# communicator_v2p5.net
KiCad netlist of a schematic drawn in EAGLE
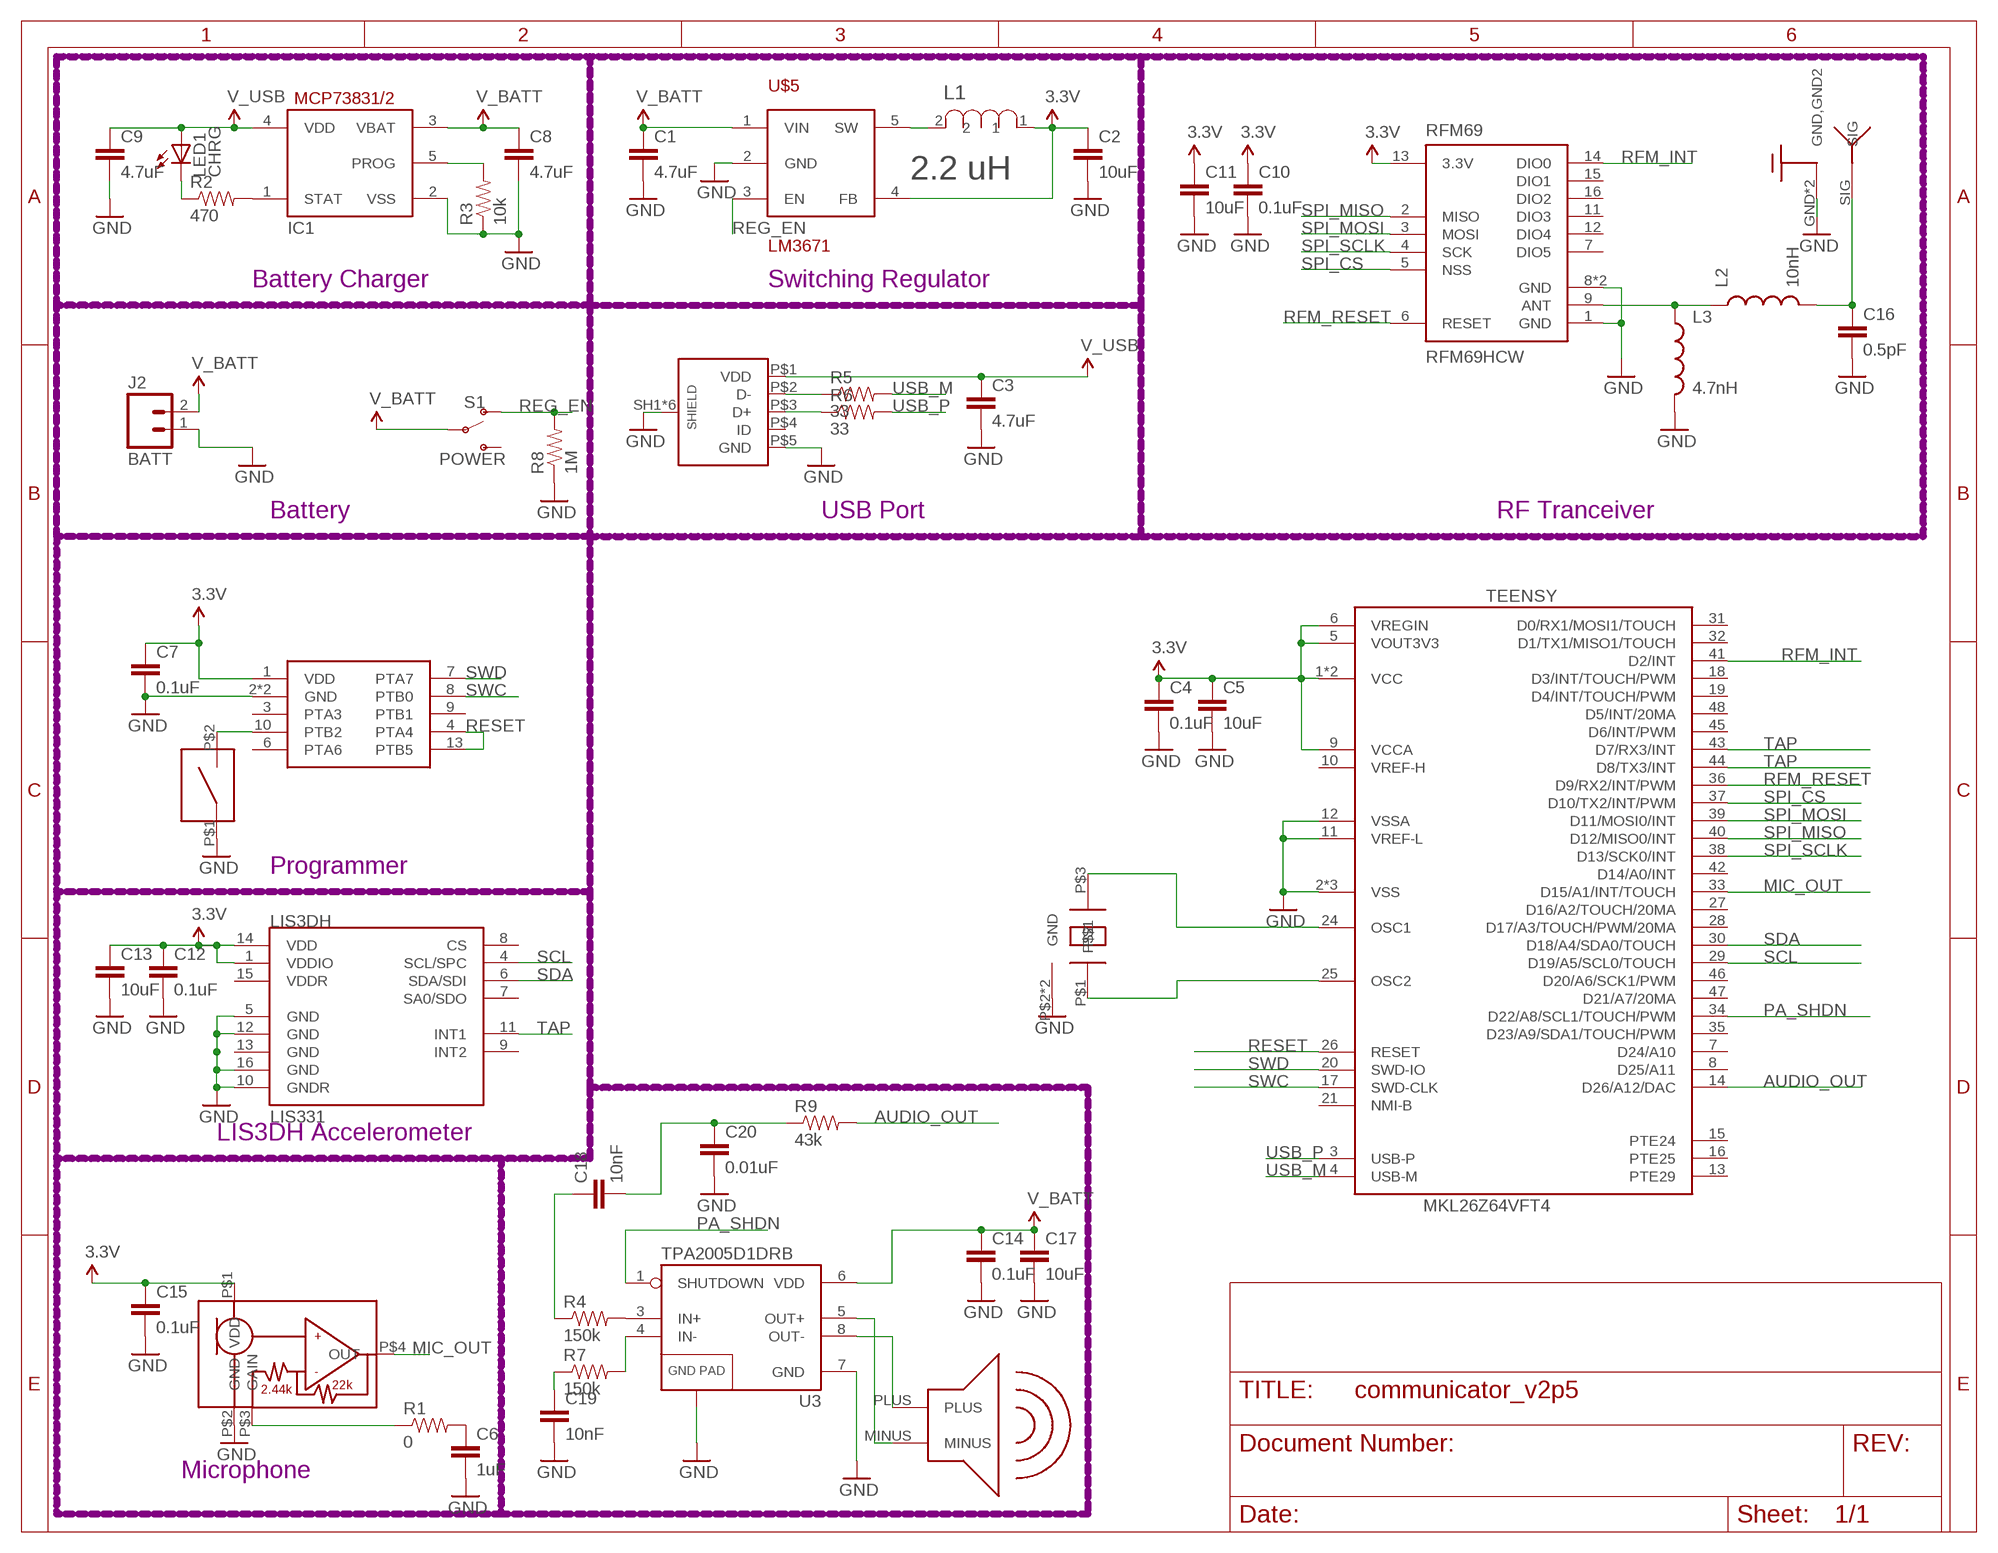
[diagram p0: schematic, sheet 1]

(export (version "E")
  (design (tool "Eeschema 10.0.6"))
  (components
    (comp (ref "3X3MM1")
      (value "CURRENT_BOOTLOADER3X3MM")
      (footprint "eagle-import:QFN50P300X300X100-17N")
      (libsource (lib "eagle-import") (part "CURRENT_BOOTLOADER3X3MM"))
    )
    (comp (ref "C1")
      (value "4.7uF")
      (footprint "eagle-import:0603-CAP")
      (libsource (lib "eagle-import") (part "0.1UF-25V(+80/-20%)(0603)"))
    )
    (comp (ref "C2")
      (value "10uF")
      (footprint "eagle-import:0603-CAP")
      (libsource (lib "eagle-import") (part "2.2UF-10V-20%(0603)"))
    )
    (comp (ref "C3")
      (value "4.7uF")
      (footprint "eagle-import:0603-CAP")
      (libsource (lib "eagle-import") (part "2.2UF-10V-20%(0603)"))
    )
    (comp (ref "C4")
      (value "0.1uF")
      (footprint "eagle-import:0603-CAP")
      (libsource (lib "eagle-import") (part "0.1UF-25V(+80/-20%)(0603)"))
    )
    (comp (ref "C5")
      (value "10uF")
      (footprint "eagle-import:0603-CAP")
      (libsource (lib "eagle-import") (part "10UF-6.3V-20%(0603)"))
    )
    (comp (ref "C6")
      (value "1uF")
      (footprint "eagle-import:0603-CAP")
      (libsource (lib "eagle-import") (part "0.1UF-25V(+80/-20%)(0603)"))
    )
    (comp (ref "C7")
      (value "0.1uF")
      (footprint "eagle-import:0603-CAP")
      (libsource (lib "eagle-import") (part "0.1UF-25V(+80/-20%)(0603)"))
    )
    (comp (ref "C8")
      (value "4.7uF")
      (footprint "eagle-import:0603-CAP")
      (libsource (lib "eagle-import") (part "4.7UF-6.3V-10%(0603)0603"))
    )
    (comp (ref "C9")
      (value "4.7uF")
      (footprint "eagle-import:0603-CAP")
      (libsource (lib "eagle-import") (part "4.7UF-6.3V-10%(0603)0603"))
    )
    (comp (ref "C10")
      (value "0.1uF")
      (footprint "eagle-import:0603-CAP")
      (libsource (lib "eagle-import") (part "0.1UF-25V(+80/-20%)(0603)"))
    )
    (comp (ref "C11")
      (value "10uF")
      (footprint "eagle-import:0603-CAP")
      (libsource (lib "eagle-import") (part "10UF-6.3V-20%(0603)"))
    )
    (comp (ref "C12")
      (value "0.1uF")
      (footprint "eagle-import:0603-CAP")
      (libsource (lib "eagle-import") (part "0.1UF-25V(+80/-20%)(0603)"))
    )
    (comp (ref "C13")
      (value "10uF")
      (footprint "eagle-import:0603-CAP")
      (libsource (lib "eagle-import") (part "10UF-6.3V-20%(0603)"))
    )
    (comp (ref "C14")
      (value "0.1uF")
      (footprint "eagle-import:0603-CAP")
      (libsource (lib "eagle-import") (part "0.1UF-25V(+80/-20%)(0603)"))
    )
    (comp (ref "C15")
      (value "0.1uF")
      (footprint "eagle-import:0603-CAP")
      (libsource (lib "eagle-import") (part "0.1UF-25V(+80/-20%)(0603)"))
    )
    (comp (ref "C16")
      (value "0.5pF")
      (footprint "eagle-import:0603-CAP")
      (libsource (lib "eagle-import") (part "0.75PF-50V(-/+.25PF)(0603)"))
    )
    (comp (ref "C17")
      (value "10uF")
      (footprint "eagle-import:0603-CAP")
      (libsource (lib "eagle-import") (part "10UF-6.3V-20%(0603)"))
    )
    (comp (ref "C18")
      (value "10nF")
      (footprint "eagle-import:0603-CAP")
      (libsource (lib "eagle-import") (part "0.1UF-25V(+80/-20%)(0603)"))
    )
    (comp (ref "C19")
      (value "10nF")
      (footprint "eagle-import:0603-CAP")
      (libsource (lib "eagle-import") (part "0.1UF-25V(+80/-20%)(0603)"))
    )
    (comp (ref "C20")
      (value "0.01uF")
      (footprint "eagle-import:0603-CAP")
      (libsource (lib "eagle-import") (part "0.1UF-25V(+80/-20%)(0603)"))
    )
    (comp (ref "IC1")
      (value "MCP73831/OT")
      (footprint "eagle-import:SOT23-5L")
      (libsource (lib "eagle-import") (part "MCP73831/OT"))
    )
    (comp (ref "J2")
      (value "BATT")
      (footprint "eagle-import:1X02")
      (libsource (lib "eagle-import") (part "M02PTH"))
    )
    (comp (ref "L1")
      (value "2.2 uH")
      (footprint "eagle-import:INDC3225X22N")
      (fields (field (name "MPN") "PM1210-2R2J-RC") (field (name "TOLERANCE") "±5 %"))
      (libsource (lib "eagle-import") (part "PM1210-2R2J-RC"))
    )
    (comp (ref "L2")
      (value "10nH")
      (footprint "eagle-import:0603")
      (libsource (lib "eagle-import") (part "INDUCTOR0603"))
    )
    (comp (ref "L3")
      (value "4.7nH")
      (footprint "eagle-import:0603")
      (libsource (lib "eagle-import") (part "INDUCTOR0603"))
    )
    (comp (ref "LED1")
      (value "CHRG")
      (footprint "eagle-import:CHIPLED_0805")
      (libsource (lib "eagle-import") (part "LEDCHIPLED_0805"))
    )
    (comp (ref "LIS3DH")
      (value "LIS331")
      (footprint "eagle-import:LGA16-3MM")
      (libsource (lib "eagle-import") (part "LIS331"))
    )
    (comp (ref "R1")
      (value "0")
      (footprint "eagle-import:0603-RES")
      (libsource (lib "eagle-import") (part "33OHM1/10W1%(0603)"))
    )
    (comp (ref "R2")
      (value "470")
      (footprint "eagle-import:0603-RES")
      (libsource (lib "eagle-import") (part "470OHM1/10W1%(0603)"))
    )
    (comp (ref "R3")
      (value "10k")
      (footprint "eagle-import:0603-RES")
      (libsource (lib "eagle-import") (part "2.55KOHM-1/10W-1%(0603)"))
    )
    (comp (ref "R4")
      (value "150k")
      (footprint "eagle-import:0603-RES")
      (libsource (lib "eagle-import") (part "33OHM1/10W1%(0603)"))
    )
    (comp (ref "R5")
      (value "33")
      (footprint "eagle-import:0603-RES")
      (libsource (lib "eagle-import") (part "33OHM1/10W1%(0603)"))
    )
    (comp (ref "R6")
      (value "33")
      (footprint "eagle-import:0603-RES")
      (libsource (lib "eagle-import") (part "33OHM1/10W1%(0603)"))
    )
    (comp (ref "R7")
      (value "150k")
      (footprint "eagle-import:0603-RES")
      (libsource (lib "eagle-import") (part "33OHM1/10W1%(0603)"))
    )
    (comp (ref "R8")
      (value "1M")
      (footprint "eagle-import:0603-RES")
      (libsource (lib "eagle-import") (part "2.55KOHM-1/10W-1%(0603)"))
    )
    (comp (ref "R9")
      (value "43k")
      (footprint "eagle-import:0603-RES")
      (libsource (lib "eagle-import") (part "33OHM1/10W1%(0603)"))
    )
    (comp (ref "RFM69")
      (value "RFM69HCW")
      (footprint "eagle-import:RFM69HCW-XXXS2")
      (libsource (lib "eagle-import") (part "RFM69HCW"))
    )
    (comp (ref "S1")
      (value "POWER")
      (footprint "eagle-import:SWITCH_SPST_SMD_A")
      (libsource (lib "eagle-import") (part "SWITCH-SPDT-SMD-RIGHT-ANGLE"))
    )
    (comp (ref "TEENSY")
      (value "MKL26Z64VFT4")
      (footprint "eagle-import:QFN50P700X700X100-49N")
      (libsource (lib "eagle-import") (part "MKL26Z64VFT4"))
    )
    (comp (ref "U$1")
      (value "ANTENNA_915MHZ")
      (footprint "eagle-import:ANTENNA_915MHZ")
      (libsource (lib "eagle-import") (part "ANTENNA_915MHZ"))
    )
    (comp (ref "U$2")
      (value "MICROPHONE")
      (footprint "eagle-import:SPU0414HR5H-SB")
      (libsource (lib "eagle-import") (part "MICROPHONE"))
    )
    (comp (ref "U$3")
      (value "SPEAKER")
      (footprint "eagle-import:PSR1511N08S3K")
      (libsource (lib "eagle-import") (part "SPEAKER"))
    )
    (comp (ref "U$4")
      (value "KXT131LHS")
      (footprint "eagle-import:KXT131LHS")
      (libsource (lib "eagle-import") (part "KXT131LHS"))
    )
    (comp (ref "U$5")
      (value "LM3671")
      (footprint "eagle-import:SOT23-5")
      (libsource (lib "eagle-import") (part "LM3671"))
    )
    (comp (ref "U$8")
      (value "MICRO_USB_B")
      (footprint "eagle-import:MICRO_USB_B")
      (libsource (lib "eagle-import") (part "MICRO_USB_B"))
    )
    (comp (ref "U$9")
      (value "TSX-3225")
      (footprint "eagle-import:TSX-3225")
      (libsource (lib "eagle-import") (part "TSX-3225"))
    )
    (comp (ref "U3")
      (value "TPA2005D1DRB")
      (footprint "eagle-import:QFN-8_PAD")
      (libsource (lib "eagle-import") (part "TPA2005D1DRB"))
    )
  )
  (nets
    (net (code "1") (name "/AUDIO_OUT") (class "Default")
      (node (ref "R9") (pin "2") (pinfunction "2_2") (pintype "passive"))
      (node (ref "TEENSY") (pin "14") (pinfunction "D26/A12/DAC_14") (pintype "bidirectional"))
    )
    (net (code "2") (name "/MIC_OUT") (class "Default")
      (node (ref "TEENSY") (pin "33") (pinfunction "D15/A1/INT/TOUCH_33") (pintype "bidirectional"))
      (node (ref "U$2") (pin "P$4") (pinfunction "OUT_P$4") (pintype "bidirectional"))
    )
    (net (code "3") (name "/PA_SHDN") (class "Default")
      (node (ref "TEENSY") (pin "34") (pinfunction "D22/A8/SCL1/TOUCH/PWM_34") (pintype "bidirectional"))
      (node (ref "U3") (pin "1") (pinfunction "SHUTDOWN_1") (pintype "input"))
    )
    (net (code "4") (name "/REG_EN") (class "Default")
      (node (ref "R8") (pin "2") (pinfunction "2_2") (pintype "passive"))
      (node (ref "S1") (pin "1") (pinfunction "O_1") (pintype "passive"))
      (node (ref "U$5") (pin "3") (pinfunction "EN_3") (pintype "bidirectional"))
    )
    (net (code "5") (name "/RESET") (class "Default")
      (node (ref "3X3MM1") (pin "13") (pinfunction "PTB5_13") (pintype "bidirectional"))
      (node (ref "3X3MM1") (pin "4") (pinfunction "PTA4_4") (pintype "bidirectional"))
      (node (ref "TEENSY") (pin "26") (pinfunction "RESET_26") (pintype "bidirectional"))
    )
    (net (code "6") (name "/RFM_INT") (class "Default")
      (node (ref "RFM69") (pin "14") (pinfunction "DIO0_14") (pintype "bidirectional"))
      (node (ref "TEENSY") (pin "41") (pinfunction "D2/INT_41") (pintype "bidirectional"))
    )
    (net (code "7") (name "/RFM_RESET") (class "Default")
      (node (ref "RFM69") (pin "6") (pinfunction "RESET_6") (pintype "input"))
      (node (ref "TEENSY") (pin "36") (pinfunction "D9/RX2/INT/PWM_36") (pintype "bidirectional"))
    )
    (net (code "8") (name "/SCL") (class "Default")
      (node (ref "LIS3DH") (pin "4") (pinfunction "SCL/SPC_4") (pintype "bidirectional"))
      (node (ref "TEENSY") (pin "29") (pinfunction "D19/A5/SCL0/TOUCH_29") (pintype "bidirectional"))
    )
    (net (code "9") (name "/SDA") (class "Default")
      (node (ref "LIS3DH") (pin "6") (pinfunction "SDA/SDI_6") (pintype "bidirectional"))
      (node (ref "TEENSY") (pin "30") (pinfunction "D18/A4/SDA0/TOUCH_30") (pintype "bidirectional"))
    )
    (net (code "10") (name "/SPI_CS") (class "Default")
      (node (ref "RFM69") (pin "5") (pinfunction "NSS_5") (pintype "input"))
      (node (ref "TEENSY") (pin "37") (pinfunction "D10/TX2/INT/PWM_37") (pintype "bidirectional"))
    )
    (net (code "11") (name "/SPI_MISO") (class "Default")
      (node (ref "RFM69") (pin "2") (pinfunction "MISO_2") (pintype "bidirectional"))
      (node (ref "TEENSY") (pin "40") (pinfunction "D12/MISO0/INT_40") (pintype "bidirectional"))
    )
    (net (code "12") (name "/SPI_MOSI") (class "Default")
      (node (ref "RFM69") (pin "3") (pinfunction "MOSI_3") (pintype "input"))
      (node (ref "TEENSY") (pin "39") (pinfunction "D11/MOSI0/INT_39") (pintype "bidirectional"))
    )
    (net (code "13") (name "/SPI_SCLK") (class "Default")
      (node (ref "RFM69") (pin "4") (pinfunction "SCK_4") (pintype "input"))
      (node (ref "TEENSY") (pin "38") (pinfunction "D13/SCK0/INT_38") (pintype "bidirectional"))
    )
    (net (code "14") (name "/SWC") (class "Default")
      (node (ref "3X3MM1") (pin "8") (pinfunction "PTB0_8") (pintype "bidirectional"))
      (node (ref "TEENSY") (pin "17") (pinfunction "SWD-CLK_17") (pintype "bidirectional"))
    )
    (net (code "15") (name "/SWD") (class "Default")
      (node (ref "3X3MM1") (pin "7") (pinfunction "PTA7_7") (pintype "bidirectional"))
      (node (ref "TEENSY") (pin "20") (pinfunction "SWD-IO_20") (pintype "bidirectional"))
    )
    (net (code "16") (name "/TAP") (class "Default")
      (node (ref "LIS3DH") (pin "11") (pinfunction "INT1_11") (pintype "bidirectional"))
      (node (ref "TEENSY") (pin "43") (pinfunction "D7/RX3/INT_43") (pintype "bidirectional"))
      (node (ref "TEENSY") (pin "44") (pinfunction "D8/TX3/INT_44") (pintype "bidirectional"))
    )
    (net (code "17") (name "/USB_M") (class "Default")
      (node (ref "R5") (pin "2") (pinfunction "2_2") (pintype "passive"))
      (node (ref "TEENSY") (pin "4") (pinfunction "USB-M_4") (pintype "bidirectional"))
    )
    (net (code "18") (name "/USB_P") (class "Default")
      (node (ref "R6") (pin "2") (pinfunction "2_2") (pintype "passive"))
      (node (ref "TEENSY") (pin "3") (pinfunction "USB-P_3") (pintype "bidirectional"))
    )
    (net (code "19") (name "3.3V") (class "Default")
      (node (ref "3X3MM1") (pin "1") (pinfunction "VDD_1") (pintype "bidirectional"))
      (node (ref "C10") (pin "1") (pinfunction "1_1") (pintype "passive"))
      (node (ref "C11") (pin "1") (pinfunction "1_1") (pintype "passive"))
      (node (ref "C12") (pin "1") (pinfunction "1_1") (pintype "passive"))
      (node (ref "C13") (pin "1") (pinfunction "1_1") (pintype "passive"))
      (node (ref "C15") (pin "1") (pinfunction "1_1") (pintype "passive"))
      (node (ref "C2") (pin "1") (pinfunction "1_1") (pintype "passive"))
      (node (ref "C4") (pin "1") (pinfunction "1_1") (pintype "passive"))
      (node (ref "C5") (pin "1") (pinfunction "1_1") (pintype "passive"))
      (node (ref "C7") (pin "1") (pinfunction "1_1") (pintype "passive"))
      (node (ref "L1") (pin "1") (pinfunction "1_1") (pintype "passive"))
      (node (ref "LIS3DH") (pin "1") (pinfunction "VDDIO_1") (pintype "bidirectional"))
      (node (ref "LIS3DH") (pin "14") (pinfunction "VDD_14") (pintype "bidirectional"))
      (node (ref "RFM69") (pin "13") (pinfunction "3.3V_13") (pintype "power_in"))
      (node (ref "TEENSY") (pin "1") (pinfunction "VCC_1") (pintype "bidirectional"))
      (node (ref "TEENSY") (pin "22") (pinfunction "VCC_22") (pintype "bidirectional"))
      (node (ref "TEENSY") (pin "5") (pinfunction "VOUT3V3_5") (pintype "bidirectional"))
      (node (ref "TEENSY") (pin "6") (pinfunction "VREGIN_6") (pintype "bidirectional"))
      (node (ref "TEENSY") (pin "9") (pinfunction "VCCA_9") (pintype "bidirectional"))
      (node (ref "U$2") (pin "P$1") (pinfunction "VDD_P$1") (pintype "bidirectional"))
      (node (ref "U$5") (pin "4") (pinfunction "FB_4") (pintype "bidirectional"))
    )
    (net (code "20") (name "GND") (class "Default")
      (node (ref "3X3MM1") (pin "17") (pinfunction "GND_17") (pintype "bidirectional"))
      (node (ref "3X3MM1") (pin "2") (pinfunction "GND_2") (pintype "bidirectional"))
      (node (ref "C1") (pin "2") (pinfunction "2_2") (pintype "passive"))
      (node (ref "C10") (pin "2") (pinfunction "2_2") (pintype "passive"))
      (node (ref "C11") (pin "2") (pinfunction "2_2") (pintype "passive"))
      (node (ref "C12") (pin "2") (pinfunction "2_2") (pintype "passive"))
      (node (ref "C13") (pin "2") (pinfunction "2_2") (pintype "passive"))
      (node (ref "C14") (pin "2") (pinfunction "2_2") (pintype "passive"))
      (node (ref "C15") (pin "2") (pinfunction "2_2") (pintype "passive"))
      (node (ref "C16") (pin "2") (pinfunction "2_2") (pintype "passive"))
      (node (ref "C17") (pin "2") (pinfunction "2_2") (pintype "passive"))
      (node (ref "C19") (pin "2") (pinfunction "2_2") (pintype "passive"))
      (node (ref "C2") (pin "2") (pinfunction "2_2") (pintype "passive"))
      (node (ref "C20") (pin "2") (pinfunction "2_2") (pintype "passive"))
      (node (ref "C3") (pin "2") (pinfunction "2_2") (pintype "passive"))
      (node (ref "C4") (pin "2") (pinfunction "2_2") (pintype "passive"))
      (node (ref "C5") (pin "2") (pinfunction "2_2") (pintype "passive"))
      (node (ref "C6") (pin "2") (pinfunction "2_2") (pintype "passive"))
      (node (ref "C7") (pin "2") (pinfunction "2_2") (pintype "passive"))
      (node (ref "C8") (pin "2") (pinfunction "2_2") (pintype "passive"))
      (node (ref "C9") (pin "2") (pinfunction "2_2") (pintype "passive"))
      (node (ref "IC1") (pin "2") (pinfunction "VSS_2") (pintype "power_in"))
      (node (ref "J2") (pin "1") (pinfunction "1_1") (pintype "passive"))
      (node (ref "L3") (pin "2") (pinfunction "2_2") (pintype "passive"))
      (node (ref "LIS3DH") (pin "10") (pinfunction "GNDR_10") (pintype "bidirectional"))
      (node (ref "LIS3DH") (pin "12") (pinfunction "GND_12") (pintype "bidirectional"))
      (node (ref "LIS3DH") (pin "16") (pinfunction "GND_16") (pintype "bidirectional"))
      (node (ref "LIS3DH") (pin "5") (pinfunction "GND_5") (pintype "bidirectional"))
      (node (ref "R3") (pin "1") (pinfunction "1_1") (pintype "passive"))
      (node (ref "R8") (pin "1") (pinfunction "1_1") (pintype "passive"))
      (node (ref "RFM69") (pin "1") (pinfunction "GND_1") (pintype "power_in"))
      (node (ref "RFM69") (pin "10") (pinfunction "GND_10") (pintype "power_in"))
      (node (ref "RFM69") (pin "8") (pinfunction "GND_8") (pintype "power_in"))
      (node (ref "TEENSY") (pin "11") (pinfunction "VREF-L_11") (pintype "bidirectional"))
      (node (ref "TEENSY") (pin "12") (pinfunction "VSSA_12") (pintype "bidirectional"))
      (node (ref "TEENSY") (pin "2") (pinfunction "VSS_2") (pintype "bidirectional"))
      (node (ref "TEENSY") (pin "23") (pinfunction "VSS_23") (pintype "bidirectional"))
      (node (ref "TEENSY") (pin "49") (pinfunction "VSS_49") (pintype "bidirectional"))
      (node (ref "U$1") (pin "GND") (pinfunction "GND,GND2_GND") (pintype "bidirectional"))
      (node (ref "U$1") (pin "GND2") (pinfunction "GND,GND2_GND2") (pintype "bidirectional"))
      (node (ref "U$2") (pin "P$2") (pinfunction "GND_P$2") (pintype "bidirectional"))
      (node (ref "U$4") (pin "P$1") (pinfunction "P$1_P$1") (pintype "bidirectional"))
      (node (ref "U$5") (pin "2") (pinfunction "GND_2") (pintype "bidirectional"))
      (node (ref "U$8") (pin "P$5") (pinfunction "GND_P$5") (pintype "bidirectional"))
      (node (ref "U$8") (pin "SH1") (pinfunction "SHIELD_SH1") (pintype "bidirectional"))
      (node (ref "U$8") (pin "SH2") (pinfunction "SHIELD_SH2") (pintype "bidirectional"))
      (node (ref "U$8") (pin "SH3") (pinfunction "SHIELD_SH3") (pintype "bidirectional"))
      (node (ref "U$8") (pin "SH4") (pinfunction "SHIELD_SH4") (pintype "bidirectional"))
      (node (ref "U$8") (pin "SH5") (pinfunction "SHIELD_SH5") (pintype "bidirectional"))
      (node (ref "U$8") (pin "SH6") (pinfunction "SHIELD_SH6") (pintype "bidirectional"))
      (node (ref "U$9") (pin "P$2") (pinfunction "GND_P$2") (pintype "bidirectional"))
      (node (ref "U$9") (pin "P$4") (pinfunction "GND_P$4") (pintype "bidirectional"))
      (node (ref "U3") (pin "10") (pinfunction "GND_10") (pintype "power_in"))
      (node (ref "U3") (pin "11") (pinfunction "GND_11") (pintype "power_in"))
      (node (ref "U3") (pin "12") (pinfunction "GND_12") (pintype "power_in"))
      (node (ref "U3") (pin "13") (pinfunction "GND_13") (pintype "power_in"))
      (node (ref "U3") (pin "7") (pinfunction "GND_7") (pintype "power_in"))
      (node (ref "U3") (pin "9") (pinfunction "GND_9") (pintype "power_in"))
    )
    (net (code "21") (name "Net-(3X3MM1-PTB2)") (class "Default")
      (node (ref "3X3MM1") (pin "10") (pinfunction "PTB2_10") (pintype "bidirectional"))
      (node (ref "U$4") (pin "P$2") (pinfunction "P$2_P$2") (pintype "bidirectional"))
    )
    (net (code "22") (name "Net-(C6-Pad1)") (class "Default")
      (node (ref "C6") (pin "1") (pinfunction "1_1") (pintype "passive"))
      (node (ref "R1") (pin "2") (pinfunction "2_2") (pintype "passive"))
    )
    (net (code "23") (name "Net-(C16-Pad1)") (class "Default")
      (node (ref "C16") (pin "1") (pinfunction "1_1") (pintype "passive"))
      (node (ref "L2") (pin "2") (pinfunction "2_2") (pintype "passive"))
      (node (ref "U$1") (pin "SIG") (pinfunction "SIG_SIG") (pintype "bidirectional"))
    )
    (net (code "24") (name "Net-(C18-Pad1)") (class "Default")
      (node (ref "C18") (pin "1") (pinfunction "1_1") (pintype "passive"))
      (node (ref "R4") (pin "1") (pinfunction "1_1") (pintype "passive"))
    )
    (net (code "25") (name "Net-(C18-Pad2)") (class "Default")
      (node (ref "C18") (pin "2") (pinfunction "2_2") (pintype "passive"))
      (node (ref "C20") (pin "1") (pinfunction "1_1") (pintype "passive"))
      (node (ref "R9") (pin "1") (pinfunction "1_1") (pintype "passive"))
    )
    (net (code "26") (name "Net-(C19-Pad1)") (class "Default")
      (node (ref "C19") (pin "1") (pinfunction "1_1") (pintype "passive"))
      (node (ref "R7") (pin "1") (pinfunction "1_1") (pintype "passive"))
    )
    (net (code "27") (name "Net-(IC1-PROG)") (class "Default")
      (node (ref "IC1") (pin "5") (pinfunction "PROG_5") (pintype "input"))
      (node (ref "R3") (pin "2") (pinfunction "2_2") (pintype "passive"))
    )
    (net (code "28") (name "Net-(IC1-STAT)") (class "Default")
      (node (ref "IC1") (pin "1") (pinfunction "STAT_1") (pintype "output"))
      (node (ref "R2") (pin "2") (pinfunction "2_2") (pintype "passive"))
    )
    (net (code "29") (name "Net-(LED1-PadC)") (class "Default")
      (node (ref "LED1") (pin "C") (pinfunction "C_C") (pintype "passive"))
      (node (ref "R2") (pin "1") (pinfunction "1_1") (pintype "passive"))
    )
    (net (code "30") (name "Net-(RFM69-ANT)") (class "Default")
      (node (ref "L2") (pin "1") (pinfunction "1_1") (pintype "passive"))
      (node (ref "L3") (pin "1") (pinfunction "1_1") (pintype "passive"))
      (node (ref "RFM69") (pin "9") (pinfunction "ANT_9") (pintype "passive"))
    )
    (net (code "31") (name "Net-(TEENSY-OSC1)") (class "Default")
      (node (ref "TEENSY") (pin "24") (pinfunction "OSC1_24") (pintype "bidirectional"))
      (node (ref "U$9") (pin "P$3") (pinfunction "P$2_P$3") (pintype "bidirectional"))
    )
    (net (code "32") (name "Net-(TEENSY-OSC2)") (class "Default")
      (node (ref "TEENSY") (pin "25") (pinfunction "OSC2_25") (pintype "bidirectional"))
      (node (ref "U$9") (pin "P$1") (pinfunction "P$1_P$1") (pintype "bidirectional"))
    )
    (net (code "33") (name "Net-(U$2-GAIN)") (class "Default")
      (node (ref "R1") (pin "1") (pinfunction "1_1") (pintype "passive"))
      (node (ref "U$2") (pin "P$3") (pinfunction "GAIN_P$3") (pintype "bidirectional"))
    )
    (net (code "34") (name "Net-(U$5-SW)") (class "Default")
      (node (ref "L1") (pin "2") (pinfunction "2_2") (pintype "passive"))
      (node (ref "U$5") (pin "5") (pinfunction "SW_5") (pintype "bidirectional"))
    )
    (net (code "35") (name "Net-(U$8-D+)") (class "Default")
      (node (ref "R6") (pin "1") (pinfunction "1_1") (pintype "passive"))
      (node (ref "U$8") (pin "P$3") (pinfunction "D+_P$3") (pintype "bidirectional"))
    )
    (net (code "36") (name "Net-(U$8-D-)") (class "Default")
      (node (ref "R5") (pin "1") (pinfunction "1_1") (pintype "passive"))
      (node (ref "U$8") (pin "P$2") (pinfunction "D-_P$2") (pintype "bidirectional"))
    )
    (net (code "37") (name "Net-(U3-IN+)") (class "Default")
      (node (ref "R4") (pin "2") (pinfunction "2_2") (pintype "passive"))
      (node (ref "U3") (pin "3") (pinfunction "IN+_3") (pintype "bidirectional"))
    )
    (net (code "38") (name "Net-(U3-IN-)") (class "Default")
      (node (ref "R7") (pin "2") (pinfunction "2_2") (pintype "passive"))
      (node (ref "U3") (pin "4") (pinfunction "IN-_4") (pintype "bidirectional"))
    )
    (net (code "39") (name "Net-(U3-OUT+)") (class "Default")
      (node (ref "U$3") (pin "MINUS") (pinfunction "MINUS_MINUS") (pintype "bidirectional"))
      (node (ref "U3") (pin "5") (pinfunction "OUT+_5") (pintype "bidirectional"))
    )
    (net (code "40") (name "Net-(U3-OUT-)") (class "Default")
      (node (ref "U$3") (pin "PLUS") (pinfunction "PLUS_PLUS") (pintype "bidirectional"))
      (node (ref "U3") (pin "8") (pinfunction "OUT-_8") (pintype "bidirectional"))
    )
    (net (code "41") (name "V_BATT") (class "Default")
      (node (ref "C1") (pin "1") (pinfunction "1_1") (pintype "passive"))
      (node (ref "C14") (pin "1") (pinfunction "1_1") (pintype "passive"))
      (node (ref "C17") (pin "1") (pinfunction "1_1") (pintype "passive"))
      (node (ref "C8") (pin "1") (pinfunction "1_1") (pintype "passive"))
      (node (ref "IC1") (pin "3") (pinfunction "VBAT_3") (pintype "bidirectional"))
      (node (ref "J2") (pin "2") (pinfunction "2_2") (pintype "passive"))
      (node (ref "S1") (pin "2") (pinfunction "P_2") (pintype "passive"))
      (node (ref "U$5") (pin "1") (pinfunction "VIN_1") (pintype "bidirectional"))
      (node (ref "U3") (pin "6") (pinfunction "VDD_6") (pintype "power_in"))
    )
    (net (code "42") (name "V_USB") (class "Default")
      (node (ref "C3") (pin "1") (pinfunction "1_1") (pintype "passive"))
      (node (ref "C9") (pin "1") (pinfunction "1_1") (pintype "passive"))
      (node (ref "IC1") (pin "4") (pinfunction "VDD_4") (pintype "power_in"))
      (node (ref "LED1") (pin "A") (pinfunction "A_A") (pintype "passive"))
      (node (ref "U$8") (pin "P$1") (pinfunction "VDD_P$1") (pintype "bidirectional"))
    )
    (net (code "43") (name "unconnected-(3X3MM1-PTA3-Pad3)") (class "Default")
      (node (ref "3X3MM1") (pin "3") (pinfunction "PTA3_3") (pintype "bidirectional"))
    )
    (net (code "44") (name "unconnected-(3X3MM1-PTA6-Pad6)") (class "Default")
      (node (ref "3X3MM1") (pin "6") (pinfunction "PTA6_6") (pintype "bidirectional"))
    )
    (net (code "45") (name "unconnected-(3X3MM1-PTB1-Pad9)") (class "Default")
      (node (ref "3X3MM1") (pin "9") (pinfunction "PTB1_9") (pintype "bidirectional"))
    )
    (net (code "46") (name "unconnected-(LIS3DH-CS-Pad8)") (class "Default")
      (node (ref "LIS3DH") (pin "8") (pinfunction "CS_8") (pintype "bidirectional"))
    )
    (net (code "47") (name "unconnected-(LIS3DH-GND-Pad13)") (class "Default")
      (node (ref "LIS3DH") (pin "13") (pinfunction "GND_13") (pintype "bidirectional"))
    )
    (net (code "48") (name "unconnected-(LIS3DH-INT2-Pad9)") (class "Default")
      (node (ref "LIS3DH") (pin "9") (pinfunction "INT2_9") (pintype "bidirectional"))
    )
    (net (code "49") (name "unconnected-(LIS3DH-SA0{slash}SDO-Pad7)") (class "Default")
      (node (ref "LIS3DH") (pin "7") (pinfunction "SA0/SDO_7") (pintype "bidirectional"))
    )
    (net (code "50") (name "unconnected-(LIS3DH-VDDR-Pad15)") (class "Default")
      (node (ref "LIS3DH") (pin "15") (pinfunction "VDDR_15") (pintype "bidirectional"))
    )
    (net (code "51") (name "unconnected-(RFM69-DIO1-Pad15)") (class "Default")
      (node (ref "RFM69") (pin "15") (pinfunction "DIO1_15") (pintype "bidirectional"))
    )
    (net (code "52") (name "unconnected-(RFM69-DIO2-Pad16)") (class "Default")
      (node (ref "RFM69") (pin "16") (pinfunction "DIO2_16") (pintype "bidirectional"))
    )
    (net (code "53") (name "unconnected-(RFM69-DIO3-Pad11)") (class "Default")
      (node (ref "RFM69") (pin "11") (pinfunction "DIO3_11") (pintype "bidirectional"))
    )
    (net (code "54") (name "unconnected-(RFM69-DIO4-Pad12)") (class "Default")
      (node (ref "RFM69") (pin "12") (pinfunction "DIO4_12") (pintype "bidirectional"))
    )
    (net (code "55") (name "unconnected-(RFM69-DIO5-Pad7)") (class "Default")
      (node (ref "RFM69") (pin "7") (pinfunction "DIO5_7") (pintype "bidirectional"))
    )
    (net (code "56") (name "unconnected-(S1-S-Pad3)") (class "Default")
      (node (ref "S1") (pin "3") (pinfunction "S_3") (pintype "passive"))
    )
    (net (code "57") (name "unconnected-(TEENSY-D0{slash}RX1{slash}MOSI1{slash}TOUCH-Pad31)") (class "Default")
      (node (ref "TEENSY") (pin "31") (pinfunction "D0/RX1/MOSI1/TOUCH_31") (pintype "bidirectional"))
    )
    (net (code "58") (name "unconnected-(TEENSY-D1{slash}TX1{slash}MISO1{slash}TOUCH-Pad32)") (class "Default")
      (node (ref "TEENSY") (pin "32") (pinfunction "D1/TX1/MISO1/TOUCH_32") (pintype "bidirectional"))
    )
    (net (code "59") (name "unconnected-(TEENSY-D3{slash}INT{slash}TOUCH{slash}PWM-Pad18)") (class "Default")
      (node (ref "TEENSY") (pin "18") (pinfunction "D3/INT/TOUCH/PWM_18") (pintype "bidirectional"))
    )
    (net (code "60") (name "unconnected-(TEENSY-D4{slash}INT{slash}TOUCH{slash}PWM-Pad19)") (class "Default")
      (node (ref "TEENSY") (pin "19") (pinfunction "D4/INT/TOUCH/PWM_19") (pintype "bidirectional"))
    )
    (net (code "61") (name "unconnected-(TEENSY-D5{slash}INT{slash}20MA-Pad48)") (class "Default")
      (node (ref "TEENSY") (pin "48") (pinfunction "D5/INT/20MA_48") (pintype "bidirectional"))
    )
    (net (code "62") (name "unconnected-(TEENSY-D6{slash}INT{slash}PWM-Pad45)") (class "Default")
      (node (ref "TEENSY") (pin "45") (pinfunction "D6/INT/PWM_45") (pintype "bidirectional"))
    )
    (net (code "63") (name "unconnected-(TEENSY-D14{slash}A0{slash}INT-Pad42)") (class "Default")
      (node (ref "TEENSY") (pin "42") (pinfunction "D14/A0/INT_42") (pintype "bidirectional"))
    )
    (net (code "64") (name "unconnected-(TEENSY-D16{slash}A2{slash}TOUCH{slash}20MA-Pad27)") (class "Default")
      (node (ref "TEENSY") (pin "27") (pinfunction "D16/A2/TOUCH/20MA_27") (pintype "bidirectional"))
    )
    (net (code "65") (name "unconnected-(TEENSY-D17{slash}A3{slash}TOUCH{slash}PWM{slash}20MA-Pad28)") (class "Default")
      (node (ref "TEENSY") (pin "28") (pinfunction "D17/A3/TOUCH/PWM/20MA_28") (pintype "bidirectional"))
    )
    (net (code "66") (name "unconnected-(TEENSY-D20{slash}A6{slash}SCK1{slash}PWM-Pad46)") (class "Default")
      (node (ref "TEENSY") (pin "46") (pinfunction "D20/A6/SCK1/PWM_46") (pintype "bidirectional"))
    )
    (net (code "67") (name "unconnected-(TEENSY-D21{slash}A7{slash}20MA-Pad47)") (class "Default")
      (node (ref "TEENSY") (pin "47") (pinfunction "D21/A7/20MA_47") (pintype "bidirectional"))
    )
    (net (code "68") (name "unconnected-(TEENSY-D23{slash}A9{slash}SDA1{slash}TOUCH{slash}PWM-Pad35)") (class "Default")
      (node (ref "TEENSY") (pin "35") (pinfunction "D23/A9/SDA1/TOUCH/PWM_35") (pintype "bidirectional"))
    )
    (net (code "69") (name "unconnected-(TEENSY-D24{slash}A10-Pad7)") (class "Default")
      (node (ref "TEENSY") (pin "7") (pinfunction "D24/A10_7") (pintype "bidirectional"))
    )
    (net (code "70") (name "unconnected-(TEENSY-D25{slash}A11-Pad8)") (class "Default")
      (node (ref "TEENSY") (pin "8") (pinfunction "D25/A11_8") (pintype "bidirectional"))
    )
    (net (code "71") (name "unconnected-(TEENSY-NMI-B-Pad21)") (class "Default")
      (node (ref "TEENSY") (pin "21") (pinfunction "NMI-B_21") (pintype "bidirectional"))
    )
    (net (code "72") (name "unconnected-(TEENSY-PTE24-Pad15)") (class "Default")
      (node (ref "TEENSY") (pin "15") (pinfunction "PTE24_15") (pintype "bidirectional"))
    )
    (net (code "73") (name "unconnected-(TEENSY-PTE25-Pad16)") (class "Default")
      (node (ref "TEENSY") (pin "16") (pinfunction "PTE25_16") (pintype "bidirectional"))
    )
    (net (code "74") (name "unconnected-(TEENSY-PTE29-Pad13)") (class "Default")
      (node (ref "TEENSY") (pin "13") (pinfunction "PTE29_13") (pintype "bidirectional"))
    )
    (net (code "75") (name "unconnected-(TEENSY-VREF-H-Pad10)") (class "Default")
      (node (ref "TEENSY") (pin "10") (pinfunction "VREF-H_10") (pintype "bidirectional"))
    )
    (net (code "76") (name "unconnected-(U$8-ID-PadP$4)") (class "Default")
      (node (ref "U$8") (pin "P$4") (pinfunction "ID_P$4") (pintype "bidirectional"))
    )
  )
)
